# 2019_Dashboard.net
KiCad netlist of a schematic drawn in EAGLE
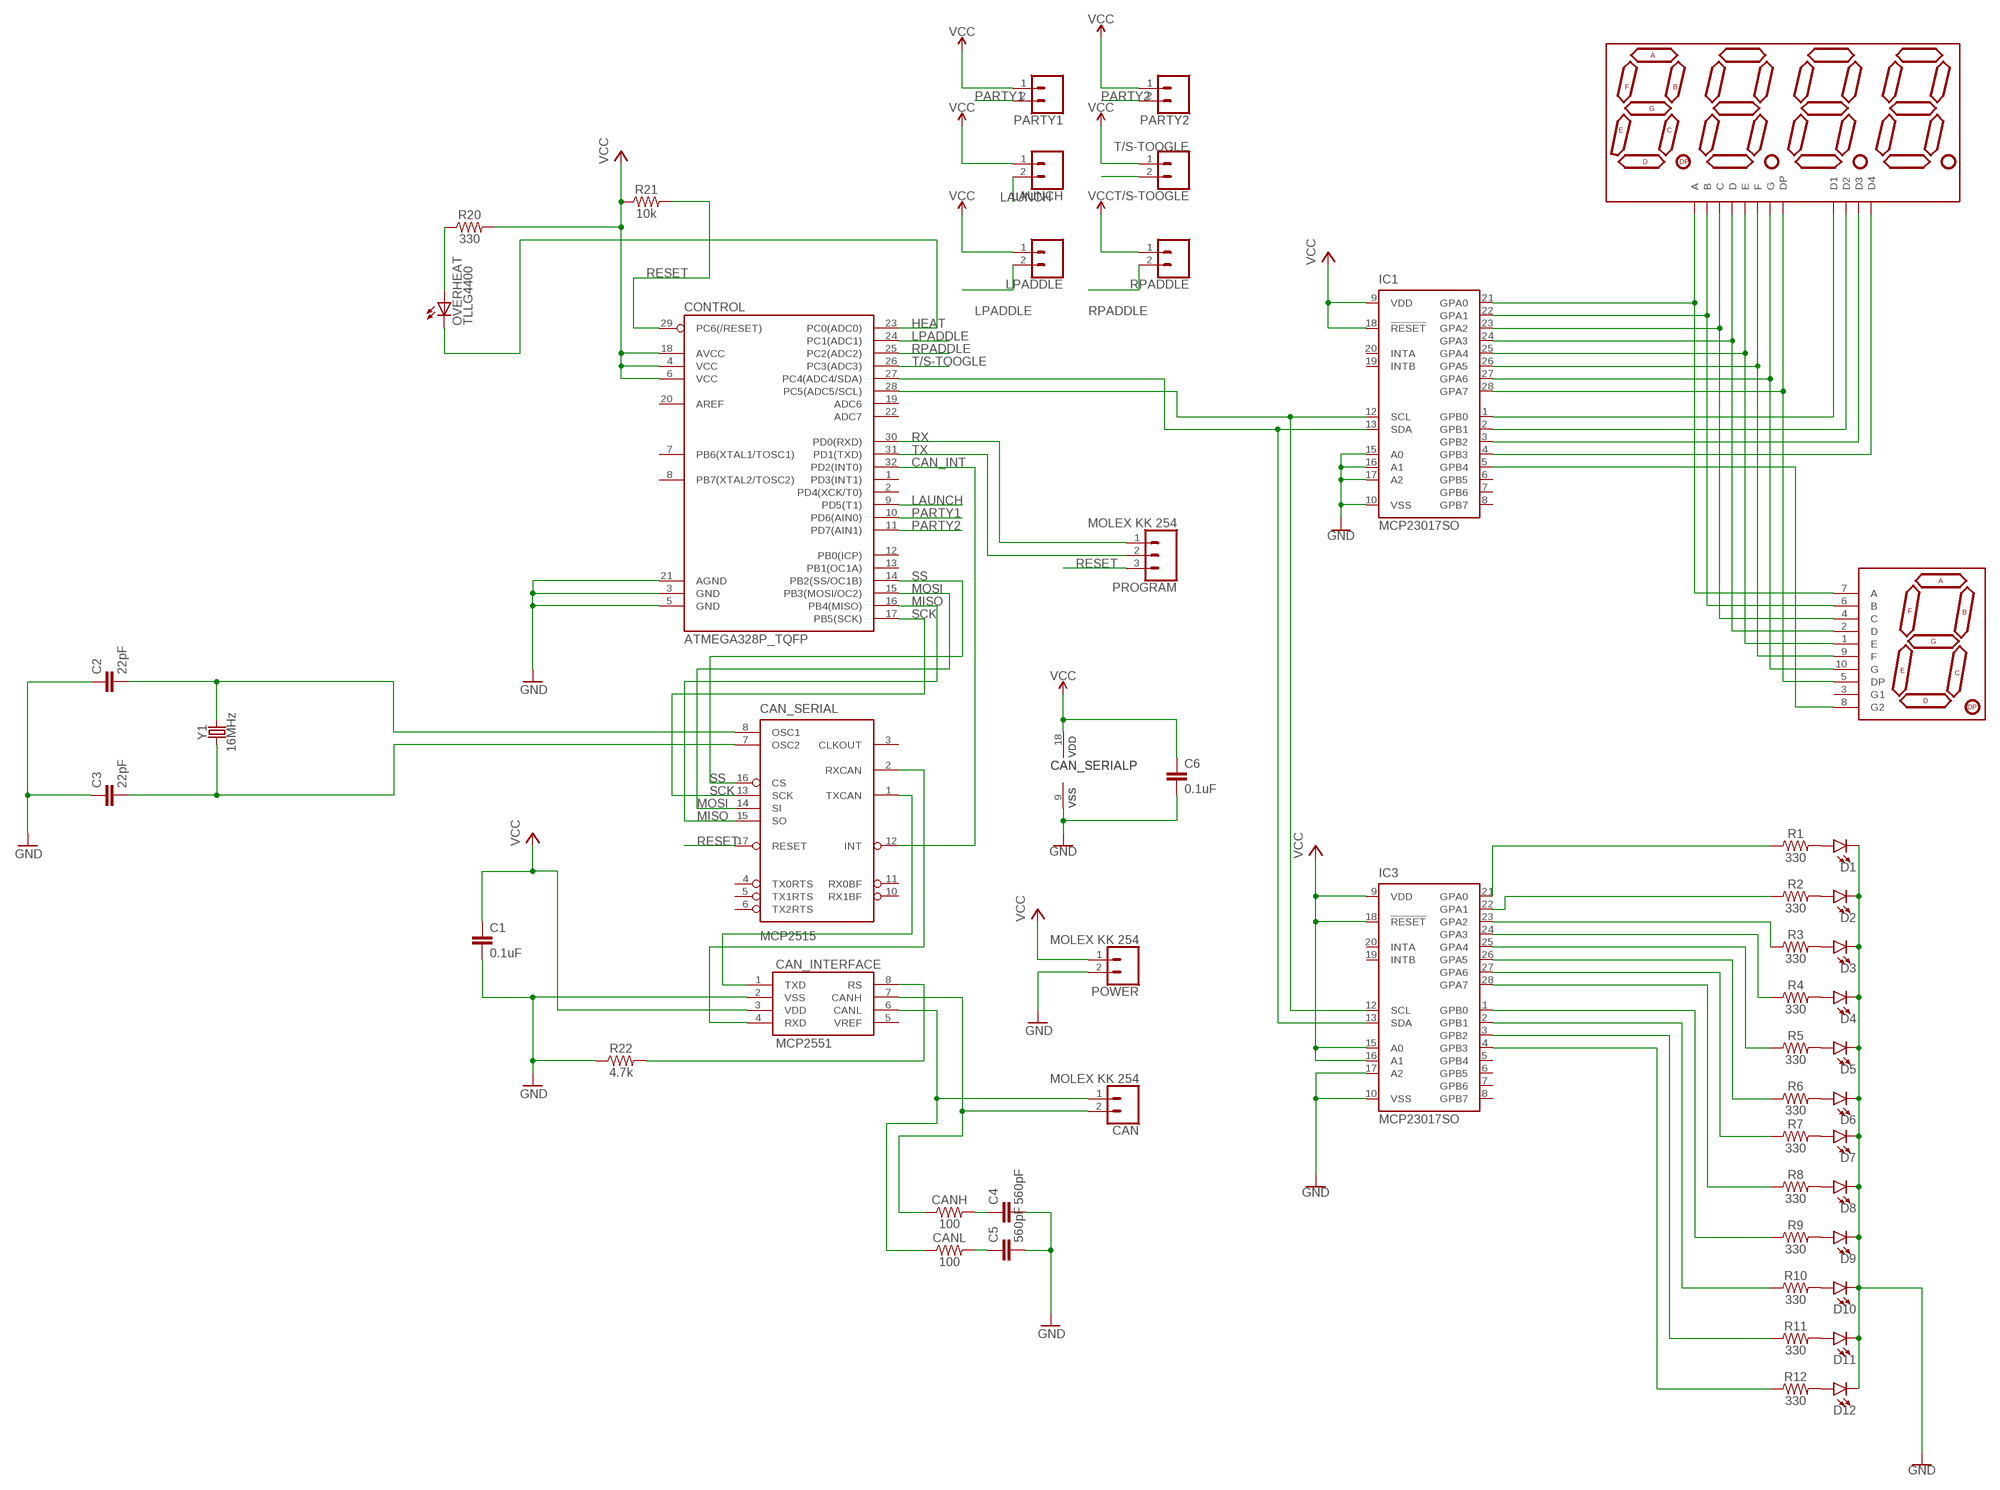
[diagram p0: schematic, sheet 1]

(export (version "E")
  (design (tool "Eeschema 10.0.6"))
  (components
    (comp (ref "C1")
      (value "0.1uF")
      (footprint "eagle-import:0603")
      (libsource (lib "eagle-import") (part "0.1UF-0603-25V-(+80/-20%)"))
    )
    (comp (ref "C2")
      (value "22pF")
      (footprint "eagle-import:0603")
      (libsource (lib "eagle-import") (part "22PF-0603-50V-5%"))
    )
    (comp (ref "C3")
      (value "22pF")
      (footprint "eagle-import:0603")
      (libsource (lib "eagle-import") (part "22PF-0603-50V-5%"))
    )
    (comp (ref "C4")
      (value "560pF")
      (footprint "eagle-import:0603")
      (libsource (lib "eagle-import") (part "560PF-0603-50V-5%"))
    )
    (comp (ref "C5")
      (value "560pF")
      (footprint "eagle-import:0603")
      (libsource (lib "eagle-import") (part "560PF-0603-50V-5%"))
    )
    (comp (ref "C6")
      (value "0.1uF")
      (footprint "eagle-import:0402")
      (libsource (lib "eagle-import") (part "0.1UF-0402-16V-10%"))
    )
    (comp (ref "CAN")
      (value "MOLEX KK 254")
      (footprint "eagle-import:1X02")
      (libsource (lib "eagle-import") (part "CONN_02"))
    )
    (comp (ref "CANH")
      (value "100")
      (footprint "eagle-import:0603")
      (libsource (lib "eagle-import") (part "100OHM-0603-1/4W-5%"))
    )
    (comp (ref "CANL")
      (value "100")
      (footprint "eagle-import:0603")
      (libsource (lib "eagle-import") (part "100OHM-0603-1/4W-5%"))
    )
    (comp (ref "CAN_INTERFACE")
      (value "MCP2551")
      (footprint "eagle-import:SO08")
      (libsource (lib "eagle-import") (part "MCP2551"))
    )
    (comp (ref "CAN_SERIAL")
      (value "MCP2515")
      (footprint "eagle-import:SO18W")
      (libsource (lib "eagle-import") (part "MCP2515(MCP2510)SO"))
    )
    (comp (ref "CONTROL")
      (value "ATMEGA328P_TQFP")
      (footprint "eagle-import:TQFP32-08")
      (libsource (lib "eagle-import") (part "ATMEGA328P_TQFP"))
    )
    (comp (ref "D1")
      (value "LED5MM")
      (footprint "eagle-import:LED_5MM")
      (libsource (lib "eagle-import") (part "LED5MM"))
    )
    (comp (ref "D2")
      (value "LED5MM")
      (footprint "eagle-import:LED_5MM")
      (libsource (lib "eagle-import") (part "LED5MM"))
    )
    (comp (ref "D3")
      (value "LED5MM")
      (footprint "eagle-import:LED_5MM")
      (libsource (lib "eagle-import") (part "LED5MM"))
    )
    (comp (ref "D4")
      (value "LED5MM")
      (footprint "eagle-import:LED_5MM")
      (libsource (lib "eagle-import") (part "LED5MM"))
    )
    (comp (ref "D5")
      (value "LED5MM")
      (footprint "eagle-import:LED_5MM")
      (libsource (lib "eagle-import") (part "LED5MM"))
    )
    (comp (ref "D6")
      (value "LED5MM")
      (footprint "eagle-import:LED_5MM")
      (libsource (lib "eagle-import") (part "LED5MM"))
    )
    (comp (ref "D7")
      (value "LED5MM")
      (footprint "eagle-import:LED_5MM")
      (libsource (lib "eagle-import") (part "LED5MM"))
    )
    (comp (ref "D8")
      (value "LED5MM")
      (footprint "eagle-import:LED_5MM")
      (libsource (lib "eagle-import") (part "LED5MM"))
    )
    (comp (ref "D9")
      (value "LED5MM")
      (footprint "eagle-import:LED_5MM")
      (libsource (lib "eagle-import") (part "LED5MM"))
    )
    (comp (ref "D10")
      (value "LED5MM")
      (footprint "eagle-import:LED_5MM")
      (libsource (lib "eagle-import") (part "LED5MM"))
    )
    (comp (ref "D11")
      (value "LED5MM")
      (footprint "eagle-import:LED_5MM")
      (libsource (lib "eagle-import") (part "LED5MM"))
    )
    (comp (ref "D12")
      (value "LED5MM")
      (footprint "eagle-import:LED_5MM")
      (libsource (lib "eagle-import") (part "LED5MM"))
    )
    (comp (ref "DISP1")
      (value "ATA8041ARBJ")
      (footprint "eagle-import:7-SEGMENT-4DIGIT-20MM")
      (libsource (lib "eagle-import") (part "7-SEGMENT-4DIGIT-20MM-RED"))
    )
    (comp (ref "IC1")
      (value "MCP23017SO")
      (footprint "eagle-import:SO28W")
      (libsource (lib "eagle-import") (part "MCP23017SO"))
    )
    (comp (ref "IC3")
      (value "MCP23017SO")
      (footprint "eagle-import:SO28W")
      (libsource (lib "eagle-import") (part "MCP23017SO"))
    )
    (comp (ref "LAUNCH")
      (value "CONN_02LOCK")
      (footprint "eagle-import:1X02_LOCK")
      (libsource (lib "eagle-import") (part "CONN_02LOCK"))
    )
    (comp (ref "LPADDLE")
      (value "CONN_02LOCK")
      (footprint "eagle-import:1X02_LOCK")
      (libsource (lib "eagle-import") (part "CONN_02LOCK"))
    )
    (comp (ref "OVERHEAT")
      (value "TLLG4400")
      (footprint "eagle-import:LED3MM")
      (fields (field (name "MF") "VISHAY SEMICONDUCTOR"))
      (libsource (lib "eagle-import") (part "TLLG4400"))
    )
    (comp (ref "PARTY1")
      (value "CONN_02LOCK")
      (footprint "eagle-import:1X02_LOCK")
      (libsource (lib "eagle-import") (part "CONN_02LOCK"))
    )
    (comp (ref "PARTY2")
      (value "CONN_02LOCK")
      (footprint "eagle-import:1X02_LOCK")
      (libsource (lib "eagle-import") (part "CONN_02LOCK"))
    )
    (comp (ref "POWER")
      (value "MOLEX KK 254")
      (footprint "eagle-import:1X02")
      (libsource (lib "eagle-import") (part "CONN_02"))
    )
    (comp (ref "PROGRAM")
      (value "MOLEX KK 254")
      (footprint "eagle-import:1X03")
      (libsource (lib "eagle-import") (part "CONN_03"))
    )
    (comp (ref "R1")
      (value "330")
      (footprint "eagle-import:0603")
      (libsource (lib "eagle-import") (part "330OHM-0603-1/10W-1%"))
    )
    (comp (ref "R2")
      (value "330")
      (footprint "eagle-import:0603")
      (libsource (lib "eagle-import") (part "330OHM-0603-1/10W-1%"))
    )
    (comp (ref "R3")
      (value "330")
      (footprint "eagle-import:0603")
      (libsource (lib "eagle-import") (part "330OHM-0603-1/10W-1%"))
    )
    (comp (ref "R4")
      (value "330")
      (footprint "eagle-import:0603")
      (libsource (lib "eagle-import") (part "330OHM-0603-1/10W-1%"))
    )
    (comp (ref "R5")
      (value "330")
      (footprint "eagle-import:0603")
      (libsource (lib "eagle-import") (part "330OHM-0603-1/10W-1%"))
    )
    (comp (ref "R6")
      (value "330")
      (footprint "eagle-import:0603")
      (libsource (lib "eagle-import") (part "330OHM-0603-1/10W-1%"))
    )
    (comp (ref "R7")
      (value "330")
      (footprint "eagle-import:0603")
      (libsource (lib "eagle-import") (part "330OHM-0603-1/10W-1%"))
    )
    (comp (ref "R8")
      (value "330")
      (footprint "eagle-import:0603")
      (libsource (lib "eagle-import") (part "330OHM-0603-1/10W-1%"))
    )
    (comp (ref "R9")
      (value "330")
      (footprint "eagle-import:0603")
      (libsource (lib "eagle-import") (part "330OHM-0603-1/10W-1%"))
    )
    (comp (ref "R10")
      (value "330")
      (footprint "eagle-import:0603")
      (libsource (lib "eagle-import") (part "330OHM-0603-1/10W-1%"))
    )
    (comp (ref "R11")
      (value "330")
      (footprint "eagle-import:0603")
      (libsource (lib "eagle-import") (part "330OHM-0603-1/10W-1%"))
    )
    (comp (ref "R12")
      (value "330")
      (footprint "eagle-import:0603")
      (libsource (lib "eagle-import") (part "330OHM-0603-1/10W-1%"))
    )
    (comp (ref "R20")
      (value "330")
      (footprint "eagle-import:0603")
      (libsource (lib "eagle-import") (part "330OHM-0603-1/10W-1%"))
    )
    (comp (ref "R21")
      (value "10k")
      (footprint "eagle-import:0603")
      (libsource (lib "eagle-import") (part "10KOHM-0603-1/10W-1%"))
    )
    (comp (ref "R22")
      (value "4.7k")
      (footprint "eagle-import:0603")
      (libsource (lib "eagle-import") (part "4.7KOHM-0603-1/10W-1%"))
    )
    (comp (ref "RPADDLE")
      (value "CONN_02LOCK")
      (footprint "eagle-import:1X02_LOCK")
      (libsource (lib "eagle-import") (part "CONN_02LOCK"))
    )
    (comp (ref "T/S-TOOGLE")
      (value "CONN_02LOCK")
      (footprint "eagle-import:1X02_LOCK")
      (libsource (lib "eagle-import") (part "CONN_02LOCK"))
    )
    (comp (ref "U$1")
      (value "YSD-1601AR4B-8")
      (footprint "eagle-import:7-SEGMENT-1_PTH")
      (libsource (lib "eagle-import") (part "7-SEGMENT-1DIGIT-1INCH-RED"))
    )
    (comp (ref "Y1")
      (value "16MHz")
      (footprint "eagle-import:HC49US")
      (libsource (lib "eagle-import") (part "CRYSTAL-16MHZPTH-HC49US"))
    )
  )
  (nets
    (net (code "1") (name "/CAN_INT") (class "Default")
      (node (ref "CAN_SERIAL") (pin "12") (pinfunction "INT_12") (pintype "output"))
      (node (ref "CONTROL") (pin "32") (pinfunction "PD2(INT0)_32") (pintype "bidirectional"))
    )
    (net (code "2") (name "/HEAT") (class "Default")
      (node (ref "CONTROL") (pin "23") (pinfunction "PC0(ADC0)_23") (pintype "bidirectional"))
      (node (ref "OVERHEAT") (pin "K") (pinfunction "C_K") (pintype "passive"))
    )
    (net (code "3") (name "/LAUNCH") (class "Default")
      (node (ref "CONTROL") (pin "9") (pinfunction "PD5(T1)_9") (pintype "bidirectional"))
      (node (ref "LAUNCH") (pin "2") (pinfunction "2_2") (pintype "passive"))
    )
    (net (code "4") (name "/LPADDLE") (class "Default")
      (node (ref "CONTROL") (pin "24") (pinfunction "PC1(ADC1)_24") (pintype "bidirectional"))
      (node (ref "LPADDLE") (pin "2") (pinfunction "2_2") (pintype "passive"))
    )
    (net (code "5") (name "/MISO") (class "Default")
      (node (ref "CAN_SERIAL") (pin "15") (pinfunction "SO_15") (pintype "output"))
      (node (ref "CONTROL") (pin "16") (pinfunction "PB4(MISO)_16") (pintype "bidirectional"))
    )
    (net (code "6") (name "/MOSI") (class "Default")
      (node (ref "CAN_SERIAL") (pin "14") (pinfunction "SI_14") (pintype "input"))
      (node (ref "CONTROL") (pin "15") (pinfunction "PB3(MOSI/OC2)_15") (pintype "bidirectional"))
    )
    (net (code "7") (name "/PARTY1") (class "Default")
      (node (ref "CONTROL") (pin "10") (pinfunction "PD6(AIN0)_10") (pintype "bidirectional"))
      (node (ref "PARTY1") (pin "2") (pinfunction "2_2") (pintype "passive"))
    )
    (net (code "8") (name "/PARTY2") (class "Default")
      (node (ref "CONTROL") (pin "11") (pinfunction "PD7(AIN1)_11") (pintype "bidirectional"))
      (node (ref "PARTY2") (pin "2") (pinfunction "2_2") (pintype "passive"))
    )
    (net (code "9") (name "/RESET") (class "Default")
      (node (ref "CAN_SERIAL") (pin "17") (pinfunction "RESET_17") (pintype "input"))
      (node (ref "CONTROL") (pin "29") (pinfunction "PC6(/RESET)_29") (pintype "bidirectional"))
      (node (ref "PROGRAM") (pin "3") (pinfunction "3_3") (pintype "passive"))
      (node (ref "R21") (pin "2") (pinfunction "2_2") (pintype "passive"))
    )
    (net (code "10") (name "/RPADDLE") (class "Default")
      (node (ref "CONTROL") (pin "25") (pinfunction "PC2(ADC2)_25") (pintype "bidirectional"))
      (node (ref "RPADDLE") (pin "2") (pinfunction "2_2") (pintype "passive"))
    )
    (net (code "11") (name "/RX") (class "Default")
      (node (ref "CONTROL") (pin "30") (pinfunction "PD0(RXD)_30") (pintype "bidirectional"))
      (node (ref "PROGRAM") (pin "1") (pinfunction "1_1") (pintype "passive"))
    )
    (net (code "12") (name "/SCK") (class "Default")
      (node (ref "CAN_SERIAL") (pin "13") (pinfunction "SCK_13") (pintype "input"))
      (node (ref "CONTROL") (pin "17") (pinfunction "PB5(SCK)_17") (pintype "bidirectional"))
    )
    (net (code "13") (name "/SS") (class "Default")
      (node (ref "CAN_SERIAL") (pin "16") (pinfunction "CS_16") (pintype "input"))
      (node (ref "CONTROL") (pin "14") (pinfunction "PB2(SS/OC1B)_14") (pintype "bidirectional"))
    )
    (net (code "14") (name "/TX") (class "Default")
      (node (ref "CONTROL") (pin "31") (pinfunction "PD1(TXD)_31") (pintype "bidirectional"))
      (node (ref "PROGRAM") (pin "2") (pinfunction "2_2") (pintype "passive"))
    )
    (net (code "15") (name "/T{slash}S-TOOGLE") (class "Default")
      (node (ref "CONTROL") (pin "26") (pinfunction "PC3(ADC3)_26") (pintype "bidirectional"))
      (node (ref "T/S-TOOGLE") (pin "2") (pinfunction "2_2") (pintype "passive"))
    )
    (net (code "16") (name "GND") (class "Default")
      (node (ref "C1") (pin "2") (pinfunction "2_2") (pintype "passive"))
      (node (ref "C2") (pin "1") (pinfunction "1_1") (pintype "passive"))
      (node (ref "C3") (pin "1") (pinfunction "1_1") (pintype "passive"))
      (node (ref "C4") (pin "2") (pinfunction "2_2") (pintype "passive"))
      (node (ref "C5") (pin "2") (pinfunction "2_2") (pintype "passive"))
      (node (ref "C6") (pin "2") (pinfunction "2_2") (pintype "passive"))
      (node (ref "CAN_INTERFACE") (pin "2") (pinfunction "VSS_2") (pintype "bidirectional"))
      (node (ref "CAN_SERIAL") (pin "9") (pinfunction "VSS_9") (pintype "power_in"))
      (node (ref "CONTROL") (pin "21") (pinfunction "AGND_21") (pintype "bidirectional"))
      (node (ref "CONTROL") (pin "3") (pinfunction "GND_3") (pintype "bidirectional"))
      (node (ref "CONTROL") (pin "5") (pinfunction "GND_5") (pintype "bidirectional"))
      (node (ref "D1") (pin "K") (pinfunction "C_K") (pintype "passive"))
      (node (ref "D10") (pin "K") (pinfunction "C_K") (pintype "passive"))
      (node (ref "D11") (pin "K") (pinfunction "C_K") (pintype "passive"))
      (node (ref "D12") (pin "K") (pinfunction "C_K") (pintype "passive"))
      (node (ref "D2") (pin "K") (pinfunction "C_K") (pintype "passive"))
      (node (ref "D3") (pin "K") (pinfunction "C_K") (pintype "passive"))
      (node (ref "D4") (pin "K") (pinfunction "C_K") (pintype "passive"))
      (node (ref "D5") (pin "K") (pinfunction "C_K") (pintype "passive"))
      (node (ref "D6") (pin "K") (pinfunction "C_K") (pintype "passive"))
      (node (ref "D7") (pin "K") (pinfunction "C_K") (pintype "passive"))
      (node (ref "D8") (pin "K") (pinfunction "C_K") (pintype "passive"))
      (node (ref "D9") (pin "K") (pinfunction "C_K") (pintype "passive"))
      (node (ref "IC1") (pin "10") (pinfunction "VSS_10") (pintype "power_in"))
      (node (ref "IC1") (pin "15") (pinfunction "A0_15") (pintype "input"))
      (node (ref "IC1") (pin "16") (pinfunction "A1_16") (pintype "input"))
      (node (ref "IC1") (pin "17") (pinfunction "A2_17") (pintype "input"))
      (node (ref "IC3") (pin "10") (pinfunction "VSS_10") (pintype "power_in"))
      (node (ref "IC3") (pin "17") (pinfunction "A2_17") (pintype "input"))
      (node (ref "POWER") (pin "2") (pinfunction "2_2") (pintype "passive"))
      (node (ref "R22") (pin "1") (pinfunction "1_1") (pintype "passive"))
    )
    (net (code "17") (name "Net-(C4-Pad1)") (class "Default")
      (node (ref "C4") (pin "1") (pinfunction "1_1") (pintype "passive"))
      (node (ref "CANH") (pin "2") (pinfunction "2_2") (pintype "passive"))
    )
    (net (code "18") (name "Net-(C5-Pad1)") (class "Default")
      (node (ref "C5") (pin "1") (pinfunction "1_1") (pintype "passive"))
      (node (ref "CANL") (pin "2") (pinfunction "2_2") (pintype "passive"))
    )
    (net (code "19") (name "Net-(CAN_INTERFACE-CANH)") (class "Default")
      (node (ref "CAN") (pin "2") (pinfunction "2_2") (pintype "passive"))
      (node (ref "CANH") (pin "1") (pinfunction "1_1") (pintype "passive"))
      (node (ref "CAN_INTERFACE") (pin "7") (pinfunction "CANH_7") (pintype "bidirectional"))
    )
    (net (code "20") (name "Net-(CAN_INTERFACE-CANL)") (class "Default")
      (node (ref "CAN") (pin "1") (pinfunction "1_1") (pintype "passive"))
      (node (ref "CANL") (pin "1") (pinfunction "1_1") (pintype "passive"))
      (node (ref "CAN_INTERFACE") (pin "6") (pinfunction "CANL_6") (pintype "bidirectional"))
    )
    (net (code "21") (name "Net-(CAN_INTERFACE-RS)") (class "Default")
      (node (ref "CAN_INTERFACE") (pin "8") (pinfunction "RS_8") (pintype "bidirectional"))
      (node (ref "R22") (pin "2") (pinfunction "2_2") (pintype "passive"))
    )
    (net (code "22") (name "Net-(CAN_INTERFACE-RXD)") (class "Default")
      (node (ref "CAN_INTERFACE") (pin "4") (pinfunction "RXD_4") (pintype "bidirectional"))
      (node (ref "CAN_SERIAL") (pin "2") (pinfunction "RXCAN_2") (pintype "input"))
    )
    (net (code "23") (name "Net-(CAN_INTERFACE-TXD)") (class "Default")
      (node (ref "CAN_INTERFACE") (pin "1") (pinfunction "TXD_1") (pintype "bidirectional"))
      (node (ref "CAN_SERIAL") (pin "1") (pinfunction "TXCAN_1") (pintype "output"))
    )
    (net (code "24") (name "Net-(CAN_SERIALA-OSC1)") (class "Default")
      (node (ref "C2") (pin "2") (pinfunction "2_2") (pintype "passive"))
      (node (ref "CAN_SERIAL") (pin "8") (pinfunction "OSC1_8") (pintype "input"))
      (node (ref "Y1") (pin "2") (pinfunction "2_2") (pintype "passive"))
    )
    (net (code "25") (name "Net-(CAN_SERIALA-OSC2)") (class "Default")
      (node (ref "C3") (pin "2") (pinfunction "2_2") (pintype "passive"))
      (node (ref "CAN_SERIAL") (pin "7") (pinfunction "OSC2_7") (pintype "output"))
      (node (ref "Y1") (pin "1") (pinfunction "1_1") (pintype "passive"))
    )
    (net (code "26") (name "Net-(CONTROL-PC4(ADC4{slash}SDA))") (class "Default")
      (node (ref "CONTROL") (pin "27") (pinfunction "PC4(ADC4/SDA)_27") (pintype "bidirectional"))
      (node (ref "IC1") (pin "13") (pinfunction "SDA_13") (pintype "bidirectional"))
      (node (ref "IC3") (pin "13") (pinfunction "SDA_13") (pintype "bidirectional"))
    )
    (net (code "27") (name "Net-(CONTROL-PC5(ADC5{slash}SCL))") (class "Default")
      (node (ref "CONTROL") (pin "28") (pinfunction "PC5(ADC5/SCL)_28") (pintype "bidirectional"))
      (node (ref "IC1") (pin "12") (pinfunction "SCL_12") (pintype "input"))
      (node (ref "IC3") (pin "12") (pinfunction "SCL_12") (pintype "input"))
    )
    (net (code "28") (name "Net-(D1-PadA)") (class "Default")
      (node (ref "D1") (pin "A") (pinfunction "A_A") (pintype "passive"))
      (node (ref "R1") (pin "2") (pinfunction "2_2") (pintype "passive"))
    )
    (net (code "29") (name "Net-(D2-PadA)") (class "Default")
      (node (ref "D2") (pin "A") (pinfunction "A_A") (pintype "passive"))
      (node (ref "R2") (pin "2") (pinfunction "2_2") (pintype "passive"))
    )
    (net (code "30") (name "Net-(D3-PadA)") (class "Default")
      (node (ref "D3") (pin "A") (pinfunction "A_A") (pintype "passive"))
      (node (ref "R3") (pin "2") (pinfunction "2_2") (pintype "passive"))
    )
    (net (code "31") (name "Net-(D4-PadA)") (class "Default")
      (node (ref "D4") (pin "A") (pinfunction "A_A") (pintype "passive"))
      (node (ref "R4") (pin "2") (pinfunction "2_2") (pintype "passive"))
    )
    (net (code "32") (name "Net-(D5-PadA)") (class "Default")
      (node (ref "D5") (pin "A") (pinfunction "A_A") (pintype "passive"))
      (node (ref "R5") (pin "2") (pinfunction "2_2") (pintype "passive"))
    )
    (net (code "33") (name "Net-(D6-PadA)") (class "Default")
      (node (ref "D6") (pin "A") (pinfunction "A_A") (pintype "passive"))
      (node (ref "R6") (pin "2") (pinfunction "2_2") (pintype "passive"))
    )
    (net (code "34") (name "Net-(D7-PadA)") (class "Default")
      (node (ref "D7") (pin "A") (pinfunction "A_A") (pintype "passive"))
      (node (ref "R7") (pin "2") (pinfunction "2_2") (pintype "passive"))
    )
    (net (code "35") (name "Net-(D8-PadA)") (class "Default")
      (node (ref "D8") (pin "A") (pinfunction "A_A") (pintype "passive"))
      (node (ref "R8") (pin "2") (pinfunction "2_2") (pintype "passive"))
    )
    (net (code "36") (name "Net-(D9-PadA)") (class "Default")
      (node (ref "D9") (pin "A") (pinfunction "A_A") (pintype "passive"))
      (node (ref "R9") (pin "2") (pinfunction "2_2") (pintype "passive"))
    )
    (net (code "37") (name "Net-(D10-PadA)") (class "Default")
      (node (ref "D10") (pin "A") (pinfunction "A_A") (pintype "passive"))
      (node (ref "R10") (pin "2") (pinfunction "2_2") (pintype "passive"))
    )
    (net (code "38") (name "Net-(D11-PadA)") (class "Default")
      (node (ref "D11") (pin "A") (pinfunction "A_A") (pintype "passive"))
      (node (ref "R11") (pin "2") (pinfunction "2_2") (pintype "passive"))
    )
    (net (code "39") (name "Net-(D12-PadA)") (class "Default")
      (node (ref "D12") (pin "A") (pinfunction "A_A") (pintype "passive"))
      (node (ref "R12") (pin "2") (pinfunction "2_2") (pintype "passive"))
    )
    (net (code "40") (name "Net-(DISP1-A)") (class "Default")
      (node (ref "DISP1") (pin "11") (pinfunction "A_11") (pintype "bidirectional"))
      (node (ref "IC1") (pin "21") (pinfunction "GPA0_21") (pintype "bidirectional"))
      (node (ref "U$1") (pin "7") (pinfunction "A_7") (pintype "bidirectional"))
    )
    (net (code "41") (name "Net-(DISP1-B)") (class "Default")
      (node (ref "DISP1") (pin "7") (pinfunction "B_7") (pintype "bidirectional"))
      (node (ref "IC1") (pin "22") (pinfunction "GPA1_22") (pintype "bidirectional"))
      (node (ref "U$1") (pin "6") (pinfunction "B_6") (pintype "bidirectional"))
    )
    (net (code "42") (name "Net-(DISP1-C)") (class "Default")
      (node (ref "DISP1") (pin "4") (pinfunction "C_4") (pintype "bidirectional"))
      (node (ref "IC1") (pin "23") (pinfunction "GPA2_23") (pintype "bidirectional"))
      (node (ref "U$1") (pin "4") (pinfunction "C_4") (pintype "bidirectional"))
    )
    (net (code "43") (name "Net-(DISP1-D)") (class "Default")
      (node (ref "DISP1") (pin "2") (pinfunction "D_2") (pintype "bidirectional"))
      (node (ref "IC1") (pin "24") (pinfunction "GPA3_24") (pintype "bidirectional"))
      (node (ref "U$1") (pin "2") (pinfunction "D_2") (pintype "bidirectional"))
    )
    (net (code "44") (name "Net-(DISP1-D1)") (class "Default")
      (node (ref "DISP1") (pin "12") (pinfunction "D1_12") (pintype "bidirectional"))
      (node (ref "IC1") (pin "1") (pinfunction "GPB0_1") (pintype "bidirectional"))
    )
    (net (code "45") (name "Net-(DISP1-D2)") (class "Default")
      (node (ref "DISP1") (pin "9") (pinfunction "D2_9") (pintype "bidirectional"))
      (node (ref "IC1") (pin "2") (pinfunction "GPB1_2") (pintype "bidirectional"))
    )
    (net (code "46") (name "Net-(DISP1-D3)") (class "Default")
      (node (ref "DISP1") (pin "8") (pinfunction "D3_8") (pintype "bidirectional"))
      (node (ref "IC1") (pin "3") (pinfunction "GPB2_3") (pintype "bidirectional"))
    )
    (net (code "47") (name "Net-(DISP1-D4)") (class "Default")
      (node (ref "DISP1") (pin "6") (pinfunction "D4_6") (pintype "bidirectional"))
      (node (ref "IC1") (pin "4") (pinfunction "GPB3_4") (pintype "bidirectional"))
    )
    (net (code "48") (name "Net-(DISP1-DP)") (class "Default")
      (node (ref "DISP1") (pin "3") (pinfunction "DP_3") (pintype "bidirectional"))
      (node (ref "IC1") (pin "28") (pinfunction "GPA7_28") (pintype "bidirectional"))
      (node (ref "U$1") (pin "5") (pinfunction "DP_5") (pintype "bidirectional"))
    )
    (net (code "49") (name "Net-(DISP1-E)") (class "Default")
      (node (ref "DISP1") (pin "1") (pinfunction "E_1") (pintype "bidirectional"))
      (node (ref "IC1") (pin "25") (pinfunction "GPA4_25") (pintype "bidirectional"))
      (node (ref "U$1") (pin "1") (pinfunction "E_1") (pintype "bidirectional"))
    )
    (net (code "50") (name "Net-(DISP1-F)") (class "Default")
      (node (ref "DISP1") (pin "10") (pinfunction "F_10") (pintype "bidirectional"))
      (node (ref "IC1") (pin "26") (pinfunction "GPA5_26") (pintype "bidirectional"))
      (node (ref "U$1") (pin "9") (pinfunction "F_9") (pintype "bidirectional"))
    )
    (net (code "51") (name "Net-(DISP1-G)") (class "Default")
      (node (ref "DISP1") (pin "5") (pinfunction "G_5") (pintype "bidirectional"))
      (node (ref "IC1") (pin "27") (pinfunction "GPA6_27") (pintype "bidirectional"))
      (node (ref "U$1") (pin "10") (pinfunction "G_10") (pintype "bidirectional"))
    )
    (net (code "52") (name "Net-(IC1-GPB4)") (class "Default")
      (node (ref "IC1") (pin "5") (pinfunction "GPB4_5") (pintype "bidirectional"))
      (node (ref "U$1") (pin "8") (pinfunction "G2_8") (pintype "bidirectional"))
    )
    (net (code "53") (name "Net-(IC3-GPA0)") (class "Default")
      (node (ref "IC3") (pin "21") (pinfunction "GPA0_21") (pintype "bidirectional"))
      (node (ref "R1") (pin "1") (pinfunction "1_1") (pintype "passive"))
    )
    (net (code "54") (name "Net-(IC3-GPA1)") (class "Default")
      (node (ref "IC3") (pin "22") (pinfunction "GPA1_22") (pintype "bidirectional"))
      (node (ref "R2") (pin "1") (pinfunction "1_1") (pintype "passive"))
    )
    (net (code "55") (name "Net-(IC3-GPA2)") (class "Default")
      (node (ref "IC3") (pin "23") (pinfunction "GPA2_23") (pintype "bidirectional"))
      (node (ref "R3") (pin "1") (pinfunction "1_1") (pintype "passive"))
    )
    (net (code "56") (name "Net-(IC3-GPA3)") (class "Default")
      (node (ref "IC3") (pin "24") (pinfunction "GPA3_24") (pintype "bidirectional"))
      (node (ref "R4") (pin "1") (pinfunction "1_1") (pintype "passive"))
    )
    (net (code "57") (name "Net-(IC3-GPA4)") (class "Default")
      (node (ref "IC3") (pin "25") (pinfunction "GPA4_25") (pintype "bidirectional"))
      (node (ref "R5") (pin "1") (pinfunction "1_1") (pintype "passive"))
    )
    (net (code "58") (name "Net-(IC3-GPA5)") (class "Default")
      (node (ref "IC3") (pin "26") (pinfunction "GPA5_26") (pintype "bidirectional"))
      (node (ref "R6") (pin "1") (pinfunction "1_1") (pintype "passive"))
    )
    (net (code "59") (name "Net-(IC3-GPA6)") (class "Default")
      (node (ref "IC3") (pin "27") (pinfunction "GPA6_27") (pintype "bidirectional"))
      (node (ref "R7") (pin "1") (pinfunction "1_1") (pintype "passive"))
    )
    (net (code "60") (name "Net-(IC3-GPA7)") (class "Default")
      (node (ref "IC3") (pin "28") (pinfunction "GPA7_28") (pintype "bidirectional"))
      (node (ref "R8") (pin "1") (pinfunction "1_1") (pintype "passive"))
    )
    (net (code "61") (name "Net-(IC3-GPB0)") (class "Default")
      (node (ref "IC3") (pin "1") (pinfunction "GPB0_1") (pintype "bidirectional"))
      (node (ref "R9") (pin "1") (pinfunction "1_1") (pintype "passive"))
    )
    (net (code "62") (name "Net-(IC3-GPB1)") (class "Default")
      (node (ref "IC3") (pin "2") (pinfunction "GPB1_2") (pintype "bidirectional"))
      (node (ref "R10") (pin "1") (pinfunction "1_1") (pintype "passive"))
    )
    (net (code "63") (name "Net-(IC3-GPB2)") (class "Default")
      (node (ref "IC3") (pin "3") (pinfunction "GPB2_3") (pintype "bidirectional"))
      (node (ref "R11") (pin "1") (pinfunction "1_1") (pintype "passive"))
    )
    (net (code "64") (name "Net-(IC3-GPB3)") (class "Default")
      (node (ref "IC3") (pin "4") (pinfunction "GPB3_4") (pintype "bidirectional"))
      (node (ref "R12") (pin "1") (pinfunction "1_1") (pintype "passive"))
    )
    (net (code "65") (name "Net-(OVERHEAT-PadA)") (class "Default")
      (node (ref "OVERHEAT") (pin "A") (pinfunction "A_A") (pintype "passive"))
      (node (ref "R20") (pin "1") (pinfunction "1_1") (pintype "passive"))
    )
    (net (code "66") (name "VCC") (class "Default")
      (node (ref "C1") (pin "1") (pinfunction "1_1") (pintype "passive"))
      (node (ref "C6") (pin "1") (pinfunction "1_1") (pintype "passive"))
      (node (ref "CAN_INTERFACE") (pin "3") (pinfunction "VDD_3") (pintype "bidirectional"))
      (node (ref "CAN_SERIAL") (pin "18") (pinfunction "VDD_18") (pintype "power_in"))
      (node (ref "CONTROL") (pin "18") (pinfunction "AVCC_18") (pintype "bidirectional"))
      (node (ref "CONTROL") (pin "4") (pinfunction "VCC_4") (pintype "bidirectional"))
      (node (ref "CONTROL") (pin "6") (pinfunction "VCC_6") (pintype "bidirectional"))
      (node (ref "IC1") (pin "18") (pinfunction "~{RESET}_18") (pintype "input"))
      (node (ref "IC1") (pin "9") (pinfunction "VDD_9") (pintype "power_in"))
      (node (ref "IC3") (pin "15") (pinfunction "A0_15") (pintype "input"))
      (node (ref "IC3") (pin "16") (pinfunction "A1_16") (pintype "input"))
      (node (ref "IC3") (pin "18") (pinfunction "~{RESET}_18") (pintype "input"))
      (node (ref "IC3") (pin "9") (pinfunction "VDD_9") (pintype "power_in"))
      (node (ref "LAUNCH") (pin "1") (pinfunction "1_1") (pintype "passive"))
      (node (ref "LPADDLE") (pin "1") (pinfunction "1_1") (pintype "passive"))
      (node (ref "PARTY1") (pin "1") (pinfunction "1_1") (pintype "passive"))
      (node (ref "PARTY2") (pin "1") (pinfunction "1_1") (pintype "passive"))
      (node (ref "POWER") (pin "1") (pinfunction "1_1") (pintype "passive"))
      (node (ref "R20") (pin "2") (pinfunction "2_2") (pintype "passive"))
      (node (ref "R21") (pin "1") (pinfunction "1_1") (pintype "passive"))
      (node (ref "RPADDLE") (pin "1") (pinfunction "1_1") (pintype "passive"))
      (node (ref "T/S-TOOGLE") (pin "1") (pinfunction "1_1") (pintype "passive"))
    )
    (net (code "67") (name "unconnected-(CAN_INTERFACE-VREF-Pad5)") (class "Default")
      (node (ref "CAN_INTERFACE") (pin "5") (pinfunction "VREF_5") (pintype "bidirectional"))
    )
    (net (code "68") (name "unconnected-(CAN_SERIALA-CLKOUT-Pad3)") (class "Default")
      (node (ref "CAN_SERIAL") (pin "3") (pinfunction "CLKOUT_3") (pintype "output"))
    )
    (net (code "69") (name "unconnected-(CAN_SERIALA-RX0BF-Pad11)") (class "Default")
      (node (ref "CAN_SERIAL") (pin "11") (pinfunction "RX0BF_11") (pintype "output"))
    )
    (net (code "70") (name "unconnected-(CAN_SERIALA-RX1BF-Pad10)") (class "Default")
      (node (ref "CAN_SERIAL") (pin "10") (pinfunction "RX1BF_10") (pintype "output"))
    )
    (net (code "71") (name "unconnected-(CAN_SERIALA-TX0RTS-Pad4)") (class "Default")
      (node (ref "CAN_SERIAL") (pin "4") (pinfunction "TX0RTS_4") (pintype "input"))
    )
    (net (code "72") (name "unconnected-(CAN_SERIALA-TX1RTS-Pad5)") (class "Default")
      (node (ref "CAN_SERIAL") (pin "5") (pinfunction "TX1RTS_5") (pintype "input"))
    )
    (net (code "73") (name "unconnected-(CAN_SERIALA-TX2RTS-Pad6)") (class "Default")
      (node (ref "CAN_SERIAL") (pin "6") (pinfunction "TX2RTS_6") (pintype "input"))
    )
    (net (code "74") (name "unconnected-(CONTROL-ADC6-Pad19)") (class "Default")
      (node (ref "CONTROL") (pin "19") (pinfunction "ADC6_19") (pintype "bidirectional"))
    )
    (net (code "75") (name "unconnected-(CONTROL-ADC7-Pad22)") (class "Default")
      (node (ref "CONTROL") (pin "22") (pinfunction "ADC7_22") (pintype "bidirectional"))
    )
    (net (code "76") (name "unconnected-(CONTROL-AREF-Pad20)") (class "Default")
      (node (ref "CONTROL") (pin "20") (pinfunction "AREF_20") (pintype "bidirectional"))
    )
    (net (code "77") (name "unconnected-(CONTROL-PB0(ICP)-Pad12)") (class "Default")
      (node (ref "CONTROL") (pin "12") (pinfunction "PB0(ICP)_12") (pintype "bidirectional"))
    )
    (net (code "78") (name "unconnected-(CONTROL-PB1(OC1A)-Pad13)") (class "Default")
      (node (ref "CONTROL") (pin "13") (pinfunction "PB1(OC1A)_13") (pintype "bidirectional"))
    )
    (net (code "79") (name "unconnected-(CONTROL-PB6(XTAL1{slash}TOSC1)-Pad7)") (class "Default")
      (node (ref "CONTROL") (pin "7") (pinfunction "PB6(XTAL1/TOSC1)_7") (pintype "bidirectional"))
    )
    (net (code "80") (name "unconnected-(CONTROL-PB7(XTAL2{slash}TOSC2)-Pad8)") (class "Default")
      (node (ref "CONTROL") (pin "8") (pinfunction "PB7(XTAL2/TOSC2)_8") (pintype "bidirectional"))
    )
    (net (code "81") (name "unconnected-(CONTROL-PD3(INT1)-Pad1)") (class "Default")
      (node (ref "CONTROL") (pin "1") (pinfunction "PD3(INT1)_1") (pintype "bidirectional"))
    )
    (net (code "82") (name "unconnected-(CONTROL-PD4(XCK{slash}T0)-Pad2)") (class "Default")
      (node (ref "CONTROL") (pin "2") (pinfunction "PD4(XCK/T0)_2") (pintype "bidirectional"))
    )
    (net (code "83") (name "unconnected-(IC1-GPB5-Pad6)") (class "Default")
      (node (ref "IC1") (pin "6") (pinfunction "GPB5_6") (pintype "bidirectional"))
    )
    (net (code "84") (name "unconnected-(IC1-GPB6-Pad7)") (class "Default")
      (node (ref "IC1") (pin "7") (pinfunction "GPB6_7") (pintype "bidirectional"))
    )
    (net (code "85") (name "unconnected-(IC1-GPB7-Pad8)") (class "Default")
      (node (ref "IC1") (pin "8") (pinfunction "GPB7_8") (pintype "bidirectional"))
    )
    (net (code "86") (name "unconnected-(IC1-INTA-Pad20)") (class "Default")
      (node (ref "IC1") (pin "20") (pinfunction "INTA_20") (pintype "output"))
    )
    (net (code "87") (name "unconnected-(IC1-INTB-Pad19)") (class "Default")
      (node (ref "IC1") (pin "19") (pinfunction "INTB_19") (pintype "output"))
    )
    (net (code "88") (name "unconnected-(IC3-GPB4-Pad5)") (class "Default")
      (node (ref "IC3") (pin "5") (pinfunction "GPB4_5") (pintype "bidirectional"))
    )
    (net (code "89") (name "unconnected-(IC3-GPB5-Pad6)") (class "Default")
      (node (ref "IC3") (pin "6") (pinfunction "GPB5_6") (pintype "bidirectional"))
    )
    (net (code "90") (name "unconnected-(IC3-GPB6-Pad7)") (class "Default")
      (node (ref "IC3") (pin "7") (pinfunction "GPB6_7") (pintype "bidirectional"))
    )
    (net (code "91") (name "unconnected-(IC3-GPB7-Pad8)") (class "Default")
      (node (ref "IC3") (pin "8") (pinfunction "GPB7_8") (pintype "bidirectional"))
    )
    (net (code "92") (name "unconnected-(IC3-INTA-Pad20)") (class "Default")
      (node (ref "IC3") (pin "20") (pinfunction "INTA_20") (pintype "output"))
    )
    (net (code "93") (name "unconnected-(IC3-INTB-Pad19)") (class "Default")
      (node (ref "IC3") (pin "19") (pinfunction "INTB_19") (pintype "output"))
    )
    (net (code "94") (name "unconnected-(U$1-G1-Pad3)") (class "Default")
      (node (ref "U$1") (pin "3") (pinfunction "G1_3") (pintype "bidirectional"))
    )
  )
)
